# V3_2.net
KiCad netlist of a schematic drawn in Altium Designer
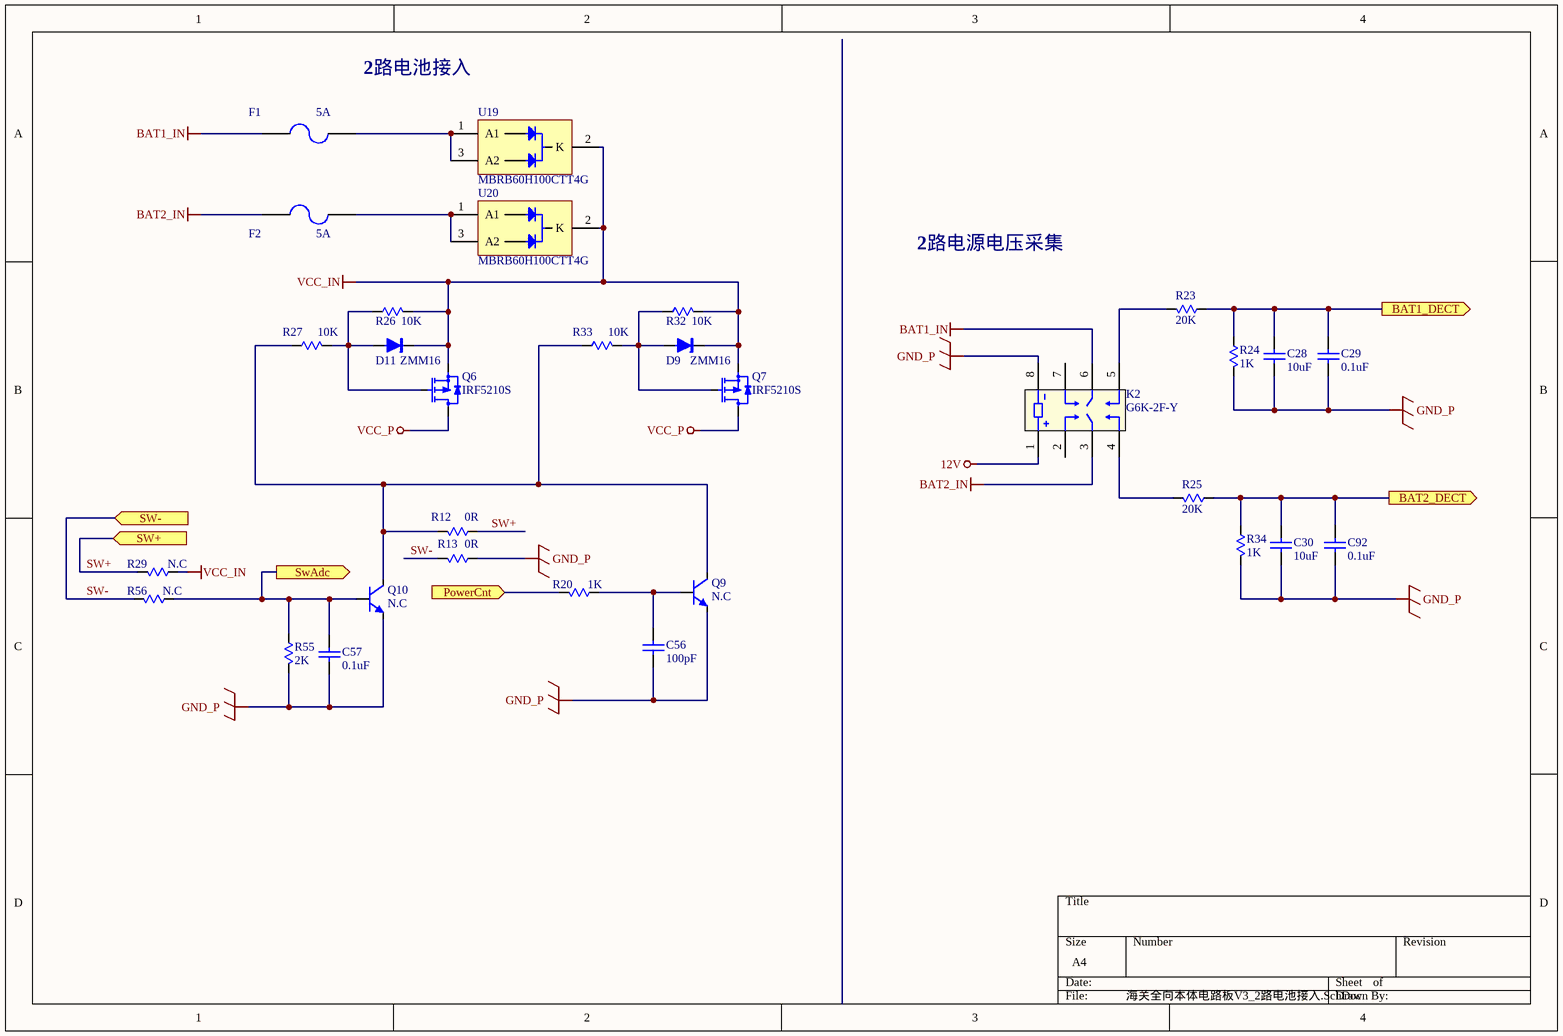
[diagram p0: 海关全向本体电路板V3_2路电池接入.SchDoc]

(export (version "E")
  (design (tool "Eeschema 10.0.6"))
  (components
    (comp (ref "C28")
      (value "10uF")
      (footprint "C0603-S")
      (description "CAP")
      (fields (field (name "PUBLISHER") "Altium Limited"))
      (libsource (lib "Passive Components Class") (part "CAP"))
    )
    (comp (ref "C29")
      (value "0.1uF")
      (footprint "C0603-S")
      (description "CAP")
      (fields (field (name "PUBLISHER") "Altium Limited"))
      (libsource (lib "Passive Components Class") (part "CAP"))
    )
    (comp (ref "C30")
      (value "10uF")
      (footprint "C0603-S")
      (description "CAP")
      (fields (field (name "PUBLISHER") "Altium Limited"))
      (libsource (lib "Passive Components Class") (part "CAP"))
    )
    (comp (ref "C56")
      (value "100pF")
      (footprint "C0603-S")
      (description "Capacitor")
      (fields (field (name "PUBLISHER") "Altium Limited"))
      (libsource (lib "Miscellaneous Devices") (part "Cap"))
    )
    (comp (ref "C57")
      (value "0.1uF")
      (footprint "C0603-S")
      (description "Capacitor")
      (fields (field (name "PUBLISHER") "Altium Limited"))
      (libsource (lib "Miscellaneous Devices") (part "Cap"))
    )
    (comp (ref "C92")
      (value "0.1uF")
      (footprint "C0603-S")
      (description "CAP")
      (fields (field (name "PUBLISHER") "Altium Limited"))
      (libsource (lib "Passive Components Class") (part "CAP"))
    )
    (comp (ref "D9")
      (value "ZMM16")
      (footprint "SOD-80-S")
      (description "Small Signal Zener Diodes")
      (libsource (lib "Passive Components Class") (part "DIODE-ZENER"))
    )
    (comp (ref "D11")
      (value "ZMM16")
      (footprint "SOD-80-S")
      (description "Small Signal Zener Diodes")
      (libsource (lib "Passive Components Class") (part "DIODE-ZENER"))
    )
    (comp (ref "F1")
      (value "5A")
      (footprint "AXIAL0.5")
      (description "Fuse")
      (libsource (lib "*") (part "FUSE2"))
    )
    (comp (ref "F2")
      (value "5A")
      (footprint "AXIAL0.5")
      (description "Fuse")
      (libsource (lib "*") (part "FUSE2"))
    )
    (comp (ref "K2")
      (value "G6K-2F-Y")
      (footprint "G6K-2F-Y")
      (libsource (lib "Productor Class") (part "G6K-2F-Y"))
    )
    (comp (ref "Q6")
      (value "IRF5210S")
      (footprint "TO-263")
      (description "P-Channel 30-V (D-S), 150 C MOSFET")
      (libsource (lib "Passive Components Class") (part "PMOS"))
    )
    (comp (ref "Q7")
      (value "IRF5210S")
      (footprint "TO-263")
      (description "P-Channel 30-V (D-S), 150 C MOSFET")
      (libsource (lib "Passive Components Class") (part "PMOS"))
    )
    (comp (ref "Q9")
      (value "N.C")
      (footprint "SOT-23")
      (description "NPN General Purpose Amplifier")
      (fields (field (name "PUBLISHER") "Altium Limited"))
      (libsource (lib "Bdmc4810") (part "NPN"))
    )
    (comp (ref "Q10")
      (value "N.C")
      (footprint "SOT-23")
      (description "NPN General Purpose Amplifier")
      (fields (field (name "PUBLISHER") "Altium Limited"))
      (libsource (lib "Bdmc4810") (part "NPN"))
    )
    (comp (ref "R12")
      (value "0R")
      (footprint "R1206-S")
      (description "Resistor")
      (fields (field (name "PUBLISHER") "Altium Limited"))
      (libsource (lib "Passive Components Class") (part "RES"))
    )
    (comp (ref "R13")
      (value "0R")
      (footprint "R1206-S")
      (description "Resistor")
      (fields (field (name "PUBLISHER") "Altium Limited"))
      (libsource (lib "Passive Components Class") (part "RES"))
    )
    (comp (ref "R20")
      (value "1K")
      (footprint "R0805-S")
      (description "Resistor")
      (fields (field (name "PUBLISHER") "Altium Limited"))
      (libsource (lib "Temp") (part "Res"))
    )
    (comp (ref "R23")
      (value "20K")
      (footprint "R0805-S")
      (description "Resistor")
      (fields (field (name "PUBLISHER") "Altium Limited"))
      (libsource (lib "") (part "RES_1"))
    )
    (comp (ref "R24")
      (value "1K")
      (footprint "R0805-S")
      (description "Resistor")
      (fields (field (name "PUBLISHER") "Altium Limited"))
      (libsource (lib "") (part "RES_1"))
    )
    (comp (ref "R25")
      (value "20K")
      (footprint "R0805-S")
      (description "Resistor")
      (fields (field (name "PUBLISHER") "Altium Limited"))
      (libsource (lib "") (part "RES_1"))
    )
    (comp (ref "R26")
      (value "10K")
      (footprint "R0805-S")
      (description "Resistor")
      (fields (field (name "PUBLISHER") "Altium Limited"))
      (libsource (lib "Temp") (part "Res"))
    )
    (comp (ref "R27")
      (value "10K")
      (footprint "R0805-S")
      (description "Resistor")
      (fields (field (name "PUBLISHER") "Altium Limited"))
      (libsource (lib "Temp") (part "Res"))
    )
    (comp (ref "R29")
      (value "N.C")
      (footprint "R0805-S")
      (description "Resistor")
      (fields (field (name "PUBLISHER") "Altium Limited"))
      (libsource (lib "Temp") (part "Res"))
    )
    (comp (ref "R32")
      (value "10K")
      (footprint "R0805-S")
      (description "Resistor")
      (fields (field (name "PUBLISHER") "Altium Limited"))
      (libsource (lib "Temp") (part "Res"))
    )
    (comp (ref "R33")
      (value "10K")
      (footprint "R0805-S")
      (description "Resistor")
      (fields (field (name "PUBLISHER") "Altium Limited"))
      (libsource (lib "Temp") (part "Res"))
    )
    (comp (ref "R34")
      (value "1K")
      (footprint "R0805-S")
      (description "Resistor")
      (fields (field (name "PUBLISHER") "Altium Limited"))
      (libsource (lib "") (part "RES_1"))
    )
    (comp (ref "R55")
      (value "2K")
      (footprint "R0805-S")
      (description "Resistor")
      (fields (field (name "PUBLISHER") "Altium Limited"))
      (libsource (lib "Temp") (part "Res"))
    )
    (comp (ref "R56")
      (value "N.C")
      (footprint "R0805-S")
      (description "Resistor")
      (fields (field (name "PUBLISHER") "Altium Limited"))
      (libsource (lib "Temp") (part "Res"))
    )
    (comp (ref "U19")
      (value "MBRB60H100CTT4G")
      (footprint "TO-263-S")
      (libsource (lib "Logic Class") (part "VB30200C"))
    )
    (comp (ref "U20")
      (value "MBRB60H100CTT4G")
      (footprint "TO-263-S")
      (libsource (lib "Logic Class") (part "VB30200C"))
    )
  )
  (nets
    (net (code "1") (name "/BAT1_DECT") (class "Default")
      (node (ref "C28") (pin "1") (pinfunction "1_1") (pintype "passive"))
      (node (ref "C29") (pin "1") (pinfunction "1_1") (pintype "passive"))
      (node (ref "R23") (pin "2") (pinfunction "2_2") (pintype "passive"))
      (node (ref "R24") (pin "2") (pinfunction "2_2") (pintype "passive"))
    )
    (net (code "2") (name "/BAT2_DECT") (class "Default")
      (node (ref "C30") (pin "1") (pinfunction "1_1") (pintype "passive"))
      (node (ref "C92") (pin "1") (pinfunction "1_1") (pintype "passive"))
      (node (ref "R25") (pin "2") (pinfunction "2_2") (pintype "passive"))
      (node (ref "R34") (pin "2") (pinfunction "2_2") (pintype "passive"))
    )
    (net (code "3") (name "/PowerCnt") (class "Default")
      (node (ref "R20") (pin "1") (pinfunction "1_1") (pintype "passive"))
    )
    (net (code "4") (name "/SW+") (class "Default")
      (node (ref "R12") (pin "1") (pinfunction "1_1") (pintype "passive"))
      (node (ref "R29") (pin "1") (pinfunction "1_1") (pintype "passive"))
    )
    (net (code "5") (name "/SW-") (class "Default")
      (node (ref "R13") (pin "2") (pinfunction "2_2") (pintype "passive"))
      (node (ref "R56") (pin "1") (pinfunction "1_1") (pintype "passive"))
    )
    (net (code "6") (name "/SwAdc") (class "Default")
      (node (ref "C57") (pin "2") (pinfunction "2_2") (pintype "passive"))
      (node (ref "Q10") (pin "1") (pinfunction "B_1") (pintype "passive"))
      (node (ref "R55") (pin "2") (pinfunction "2_2") (pintype "passive"))
      (node (ref "R56") (pin "2") (pinfunction "2_2") (pintype "passive"))
    )
    (net (code "7") (name "12V") (class "Default")
      (node (ref "K2") (pin "1") (pinfunction "1_1") (pintype "passive"))
    )
    (net (code "8") (name "BAT1_IN") (class "Default")
      (node (ref "F1") (pin "1") (pinfunction "1_1") (pintype "passive"))
      (node (ref "K2") (pin "6") (pinfunction "6_6") (pintype "passive"))
    )
    (net (code "9") (name "BAT2_IN") (class "Default")
      (node (ref "F2") (pin "1") (pinfunction "1_1") (pintype "passive"))
      (node (ref "K2") (pin "3") (pinfunction "3_3") (pintype "passive"))
    )
    (net (code "10") (name "GND_P") (class "Default")
      (node (ref "C28") (pin "2") (pinfunction "2_2") (pintype "passive"))
      (node (ref "C29") (pin "2") (pinfunction "2_2") (pintype "passive"))
      (node (ref "C30") (pin "2") (pinfunction "2_2") (pintype "passive"))
      (node (ref "C56") (pin "1") (pinfunction "1_1") (pintype "passive"))
      (node (ref "C57") (pin "1") (pinfunction "1_1") (pintype "passive"))
      (node (ref "C92") (pin "2") (pinfunction "2_2") (pintype "passive"))
      (node (ref "K2") (pin "8") (pinfunction "8_8") (pintype "passive"))
      (node (ref "Q10") (pin "2") (pinfunction "E_2") (pintype "passive"))
      (node (ref "Q9") (pin "2") (pinfunction "E_2") (pintype "passive"))
      (node (ref "R13") (pin "1") (pinfunction "1_1") (pintype "passive"))
      (node (ref "R24") (pin "1") (pinfunction "1_1") (pintype "passive"))
      (node (ref "R34") (pin "1") (pinfunction "1_1") (pintype "passive"))
      (node (ref "R55") (pin "1") (pinfunction "1_1") (pintype "passive"))
    )
    (net (code "11") (name "Net-(D9-A)") (class "Default")
      (node (ref "D9") (pin "1") (pinfunction "A_1") (pintype "passive"))
      (node (ref "Q7") (pin "1") (pinfunction "G_1") (pintype "passive"))
      (node (ref "R32") (pin "2") (pinfunction "2_2") (pintype "passive"))
      (node (ref "R33") (pin "1") (pinfunction "1_1") (pintype "passive"))
    )
    (net (code "12") (name "Net-(D11-A)") (class "Default")
      (node (ref "D11") (pin "1") (pinfunction "A_1") (pintype "passive"))
      (node (ref "Q6") (pin "1") (pinfunction "G_1") (pintype "passive"))
      (node (ref "R26") (pin "2") (pinfunction "2_2") (pintype "passive"))
      (node (ref "R27") (pin "1") (pinfunction "1_1") (pintype "passive"))
    )
    (net (code "13") (name "Net-(K2-Pad4)") (class "Default")
      (node (ref "K2") (pin "4") (pinfunction "4_4") (pintype "passive"))
      (node (ref "R25") (pin "1") (pinfunction "1_1") (pintype "passive"))
    )
    (net (code "14") (name "Net-(K2-Pad5)") (class "Default")
      (node (ref "K2") (pin "5") (pinfunction "5_5") (pintype "passive"))
      (node (ref "R23") (pin "1") (pinfunction "1_1") (pintype "passive"))
    )
    (net (code "15") (name "Net-(Q9-B)") (class "Default")
      (node (ref "C56") (pin "2") (pinfunction "2_2") (pintype "passive"))
      (node (ref "Q9") (pin "1") (pinfunction "B_1") (pintype "passive"))
      (node (ref "R20") (pin "2") (pinfunction "2_2") (pintype "passive"))
    )
    (net (code "16") (name "Net-(Q10-C)") (class "Default")
      (node (ref "Q10") (pin "3") (pinfunction "C_3") (pintype "passive"))
      (node (ref "Q9") (pin "3") (pinfunction "C_3") (pintype "passive"))
      (node (ref "R12") (pin "2") (pinfunction "2_2") (pintype "passive"))
      (node (ref "R27") (pin "2") (pinfunction "2_2") (pintype "passive"))
      (node (ref "R33") (pin "2") (pinfunction "2_2") (pintype "passive"))
    )
    (net (code "17") (name "Net-(U19-A1)") (class "Default")
      (node (ref "F1") (pin "2") (pinfunction "2_2") (pintype "passive"))
      (node (ref "U19") (pin "1") (pinfunction "A1_1") (pintype "passive"))
      (node (ref "U19") (pin "3") (pinfunction "A2_3") (pintype "passive"))
    )
    (net (code "18") (name "Net-(U20-A1)") (class "Default")
      (node (ref "F2") (pin "2") (pinfunction "2_2") (pintype "passive"))
      (node (ref "U20") (pin "1") (pinfunction "A1_1") (pintype "passive"))
      (node (ref "U20") (pin "3") (pinfunction "A2_3") (pintype "passive"))
    )
    (net (code "19") (name "VCC_IN") (class "Default")
      (node (ref "D11") (pin "2") (pinfunction "K_2") (pintype "passive"))
      (node (ref "D9") (pin "2") (pinfunction "K_2") (pintype "passive"))
      (node (ref "Q6") (pin "3") (pinfunction "S_3") (pintype "passive"))
      (node (ref "Q7") (pin "3") (pinfunction "S_3") (pintype "passive"))
      (node (ref "R26") (pin "1") (pinfunction "1_1") (pintype "passive"))
      (node (ref "R29") (pin "2") (pinfunction "2_2") (pintype "passive"))
      (node (ref "R32") (pin "1") (pinfunction "1_1") (pintype "passive"))
      (node (ref "U19") (pin "2") (pinfunction "K_2") (pintype "passive"))
      (node (ref "U20") (pin "2") (pinfunction "K_2") (pintype "passive"))
    )
    (net (code "20") (name "VCC_P") (class "Default")
      (node (ref "Q6") (pin "2") (pinfunction "D_2") (pintype "passive"))
      (node (ref "Q7") (pin "2") (pinfunction "D_2") (pintype "passive"))
    )
    (net (code "21") (name "unconnected-(K2-Pad2)") (class "Default")
      (node (ref "K2") (pin "2") (pinfunction "2_2") (pintype "passive"))
    )
    (net (code "22") (name "unconnected-(K2-Pad7)") (class "Default")
      (node (ref "K2") (pin "7") (pinfunction "7_7") (pintype "passive"))
    )
  )
)
